# UWB_F3_CAN_UWB_layout.net
KiCad netlist of a schematic drawn in Altium Designer
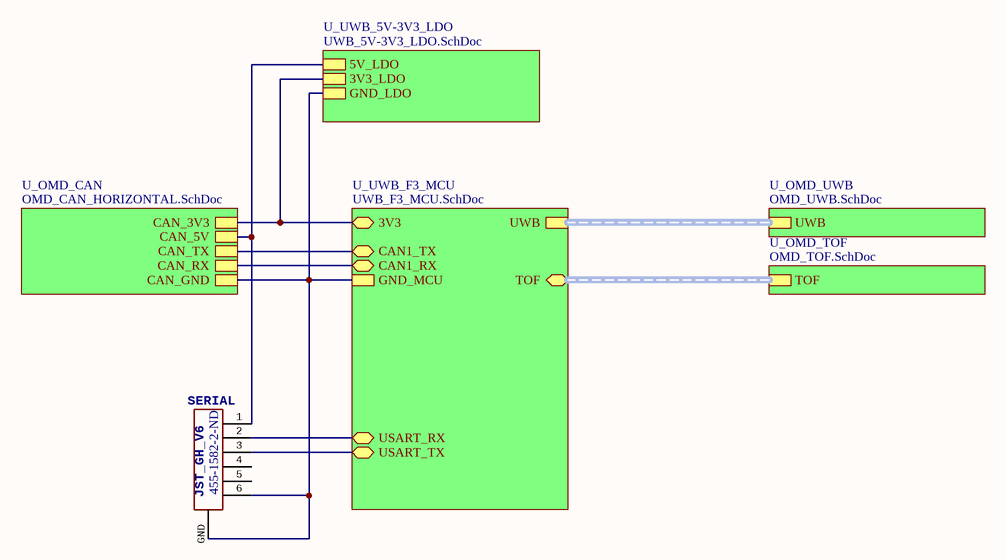
[diagram p0: UWB_F3_CAN_UWB_layout.SchDoc]

(export (version "E")
  (design (tool "Eeschema 10.0.6"))
  (components
    (comp (ref "SERIAL")
      (value "JST_GH_V6")
      (footprint "JST_GH_V6")
      (description "BM06B-GHS-TBT")
      (fields (field (name "SUPPLIER PART NUMBER 1") "455-1582-2-ND"))
      (libsource (lib "CB_SCI_AERO") (part "JST_GH_V6"))
    )
  )
  (nets
    (net (code "2") (name "/5V_LDO") (class "Default")
      (node (ref "SERIAL") (pin "1") (pinfunction "1_1") (pintype "passive"))
    )
    (net (code "5") (name "/CAN_GND") (class "Default")
      (node (ref "SERIAL") (pin "6") (pinfunction "6_6") (pintype "passive"))
      (node (ref "SERIAL") (pin "GND") (pinfunction "GND_GND") (pintype "passive"))
    )
    (net (code "7") (name "/USART_RX") (class "Default")
      (node (ref "SERIAL") (pin "2") (pinfunction "2_2") (pintype "passive"))
    )
    (net (code "8") (name "/USART_TX") (class "Default")
      (node (ref "SERIAL") (pin "3") (pinfunction "3_3") (pintype "passive"))
    )
    (net (code "10") (name "unconnected-(SERIAL-Pad4)") (class "Default")
      (node (ref "SERIAL") (pin "4") (pinfunction "4_4") (pintype "passive"))
    )
    (net (code "11") (name "unconnected-(SERIAL-Pad5)") (class "Default")
      (node (ref "SERIAL") (pin "5") (pinfunction "5_5") (pintype "passive"))
    )
  )
)
